# KeyPad.net
KiCad netlist of a schematic drawn in Altium Designer
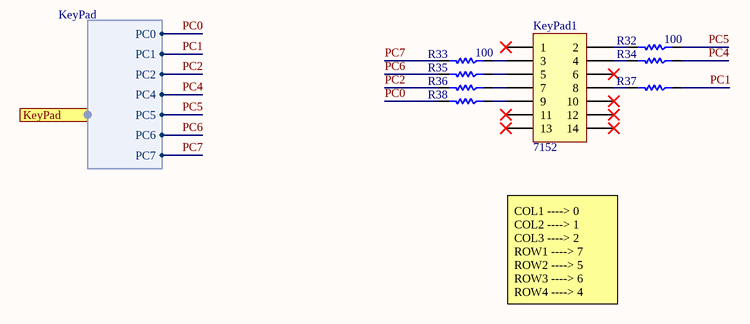
[diagram p0: KeyPad.SchDoc]

(export (version "E")
  (design (tool "Eeschema 10.0.6"))
  (components
    (comp (ref "KeyPad1")
      (value "7x2")
      (footprint "HDR_THT_7x2M_2.54mm")
      (description "Header, dual row, 14 pin")
      (fields (field (name "INFLOW") "7152") (field (name "VALIDATION") "NT"))
      (libsource (lib "aKaReZa") (part "Con_MPH_7x2_V_THT_2.54"))
    )
    (comp (ref "R32")
      (value "100")
      (footprint "RES 1206 (3216X08L)")
      (description "Resistor")
      (fields (field (name "VALIDATION") "Valid"))
      (libsource (lib "aKaReZa") (part "Res_SMD_1206"))
    )
    (comp (ref "R33")
      (value "100")
      (footprint "RES 1206 (3216X08L)")
      (description "Resistor")
      (fields (field (name "VALIDATION") "Valid"))
      (libsource (lib "aKaReZa") (part "Res_SMD_1206"))
    )
    (comp (ref "R34")
      (value "~")
      (footprint "RES 1206 (3216X08L)")
      (description "Resistor")
      (fields (field (name "VALIDATION") "Valid"))
      (libsource (lib "aKaReZa") (part "Res_SMD_1206"))
    )
    (comp (ref "R35")
      (value "~")
      (footprint "RES 1206 (3216X08L)")
      (description "Resistor")
      (fields (field (name "VALIDATION") "Valid"))
      (libsource (lib "aKaReZa") (part "Res_SMD_1206"))
    )
    (comp (ref "R36")
      (value "~")
      (footprint "RES 1206 (3216X08L)")
      (description "Resistor")
      (fields (field (name "VALIDATION") "Valid"))
      (libsource (lib "aKaReZa") (part "Res_SMD_1206"))
    )
    (comp (ref "R37")
      (value "~")
      (footprint "RES 1206 (3216X08L)")
      (description "Resistor")
      (fields (field (name "VALIDATION") "Valid"))
      (libsource (lib "aKaReZa") (part "Res_SMD_1206"))
    )
    (comp (ref "R38")
      (value "~")
      (footprint "RES 1206 (3216X08L)")
      (description "Resistor")
      (fields (field (name "VALIDATION") "Valid"))
      (libsource (lib "aKaReZa") (part "Res_SMD_1206"))
    )
  )
  (nets
    (net (code "2") (name "/PC0") (class "Default")
      (node (ref "R38") (pin "2") (pinfunction "2_2") (pintype "passive"))
    )
    (net (code "3") (name "/PC1") (class "Default")
      (node (ref "R37") (pin "1") (pinfunction "1_1") (pintype "passive"))
    )
    (net (code "4") (name "/PC2") (class "Default")
      (node (ref "R36") (pin "2") (pinfunction "2_2") (pintype "passive"))
    )
    (net (code "5") (name "/PC4") (class "Default")
      (node (ref "R34") (pin "1") (pinfunction "1_1") (pintype "passive"))
    )
    (net (code "6") (name "/PC5") (class "Default")
      (node (ref "R32") (pin "1") (pinfunction "1_1") (pintype "passive"))
    )
    (net (code "7") (name "/PC6") (class "Default")
      (node (ref "R35") (pin "2") (pinfunction "2_2") (pintype "passive"))
    )
    (net (code "8") (name "/PC7") (class "Default")
      (node (ref "R33") (pin "2") (pinfunction "2_2") (pintype "passive"))
    )
    (net (code "10") (name "Net-(KeyPad1-Pad2)") (class "Default")
      (node (ref "KeyPad1") (pin "2") (pinfunction "2_2") (pintype "passive"))
      (node (ref "R32") (pin "2") (pinfunction "2_2") (pintype "passive"))
    )
    (net (code "11") (name "Net-(KeyPad1-Pad3)") (class "Default")
      (node (ref "KeyPad1") (pin "3") (pinfunction "3_3") (pintype "passive"))
      (node (ref "R33") (pin "1") (pinfunction "1_1") (pintype "passive"))
    )
    (net (code "12") (name "Net-(KeyPad1-Pad4)") (class "Default")
      (node (ref "KeyPad1") (pin "4") (pinfunction "4_4") (pintype "passive"))
      (node (ref "R34") (pin "2") (pinfunction "2_2") (pintype "passive"))
    )
    (net (code "13") (name "Net-(KeyPad1-Pad5)") (class "Default")
      (node (ref "KeyPad1") (pin "5") (pinfunction "5_5") (pintype "passive"))
      (node (ref "R35") (pin "1") (pinfunction "1_1") (pintype "passive"))
    )
    (net (code "14") (name "Net-(KeyPad1-Pad7)") (class "Default")
      (node (ref "KeyPad1") (pin "7") (pinfunction "7_7") (pintype "passive"))
      (node (ref "R36") (pin "1") (pinfunction "1_1") (pintype "passive"))
    )
    (net (code "15") (name "Net-(KeyPad1-Pad8)") (class "Default")
      (node (ref "KeyPad1") (pin "8") (pinfunction "8_8") (pintype "passive"))
      (node (ref "R37") (pin "2") (pinfunction "2_2") (pintype "passive"))
    )
    (net (code "16") (name "Net-(KeyPad1-Pad9)") (class "Default")
      (node (ref "KeyPad1") (pin "9") (pinfunction "9_9") (pintype "passive"))
      (node (ref "R38") (pin "1") (pinfunction "1_1") (pintype "passive"))
    )
    (net (code "17") (name "unconnected-(KeyPad1-Pad1)") (class "Default")
      (node (ref "KeyPad1") (pin "1") (pinfunction "1_1") (pintype "passive+no_connect"))
    )
    (net (code "18") (name "unconnected-(KeyPad1-Pad6)") (class "Default")
      (node (ref "KeyPad1") (pin "6") (pinfunction "6_6") (pintype "passive+no_connect"))
    )
    (net (code "19") (name "unconnected-(KeyPad1-Pad10)") (class "Default")
      (node (ref "KeyPad1") (pin "10") (pinfunction "10_10") (pintype "passive+no_connect"))
    )
    (net (code "20") (name "unconnected-(KeyPad1-Pad11)") (class "Default")
      (node (ref "KeyPad1") (pin "11") (pinfunction "11_11") (pintype "passive+no_connect"))
    )
    (net (code "21") (name "unconnected-(KeyPad1-Pad12)") (class "Default")
      (node (ref "KeyPad1") (pin "12") (pinfunction "12_12") (pintype "passive+no_connect"))
    )
    (net (code "22") (name "unconnected-(KeyPad1-Pad13)") (class "Default")
      (node (ref "KeyPad1") (pin "13") (pinfunction "13_13") (pintype "passive+no_connect"))
    )
    (net (code "23") (name "unconnected-(KeyPad1-Pad14)") (class "Default")
      (node (ref "KeyPad1") (pin "14") (pinfunction "14_14") (pintype "passive+no_connect"))
    )
  )
)
